# bal_part.net
KiCad netlist of a schematic drawn in EAGLE
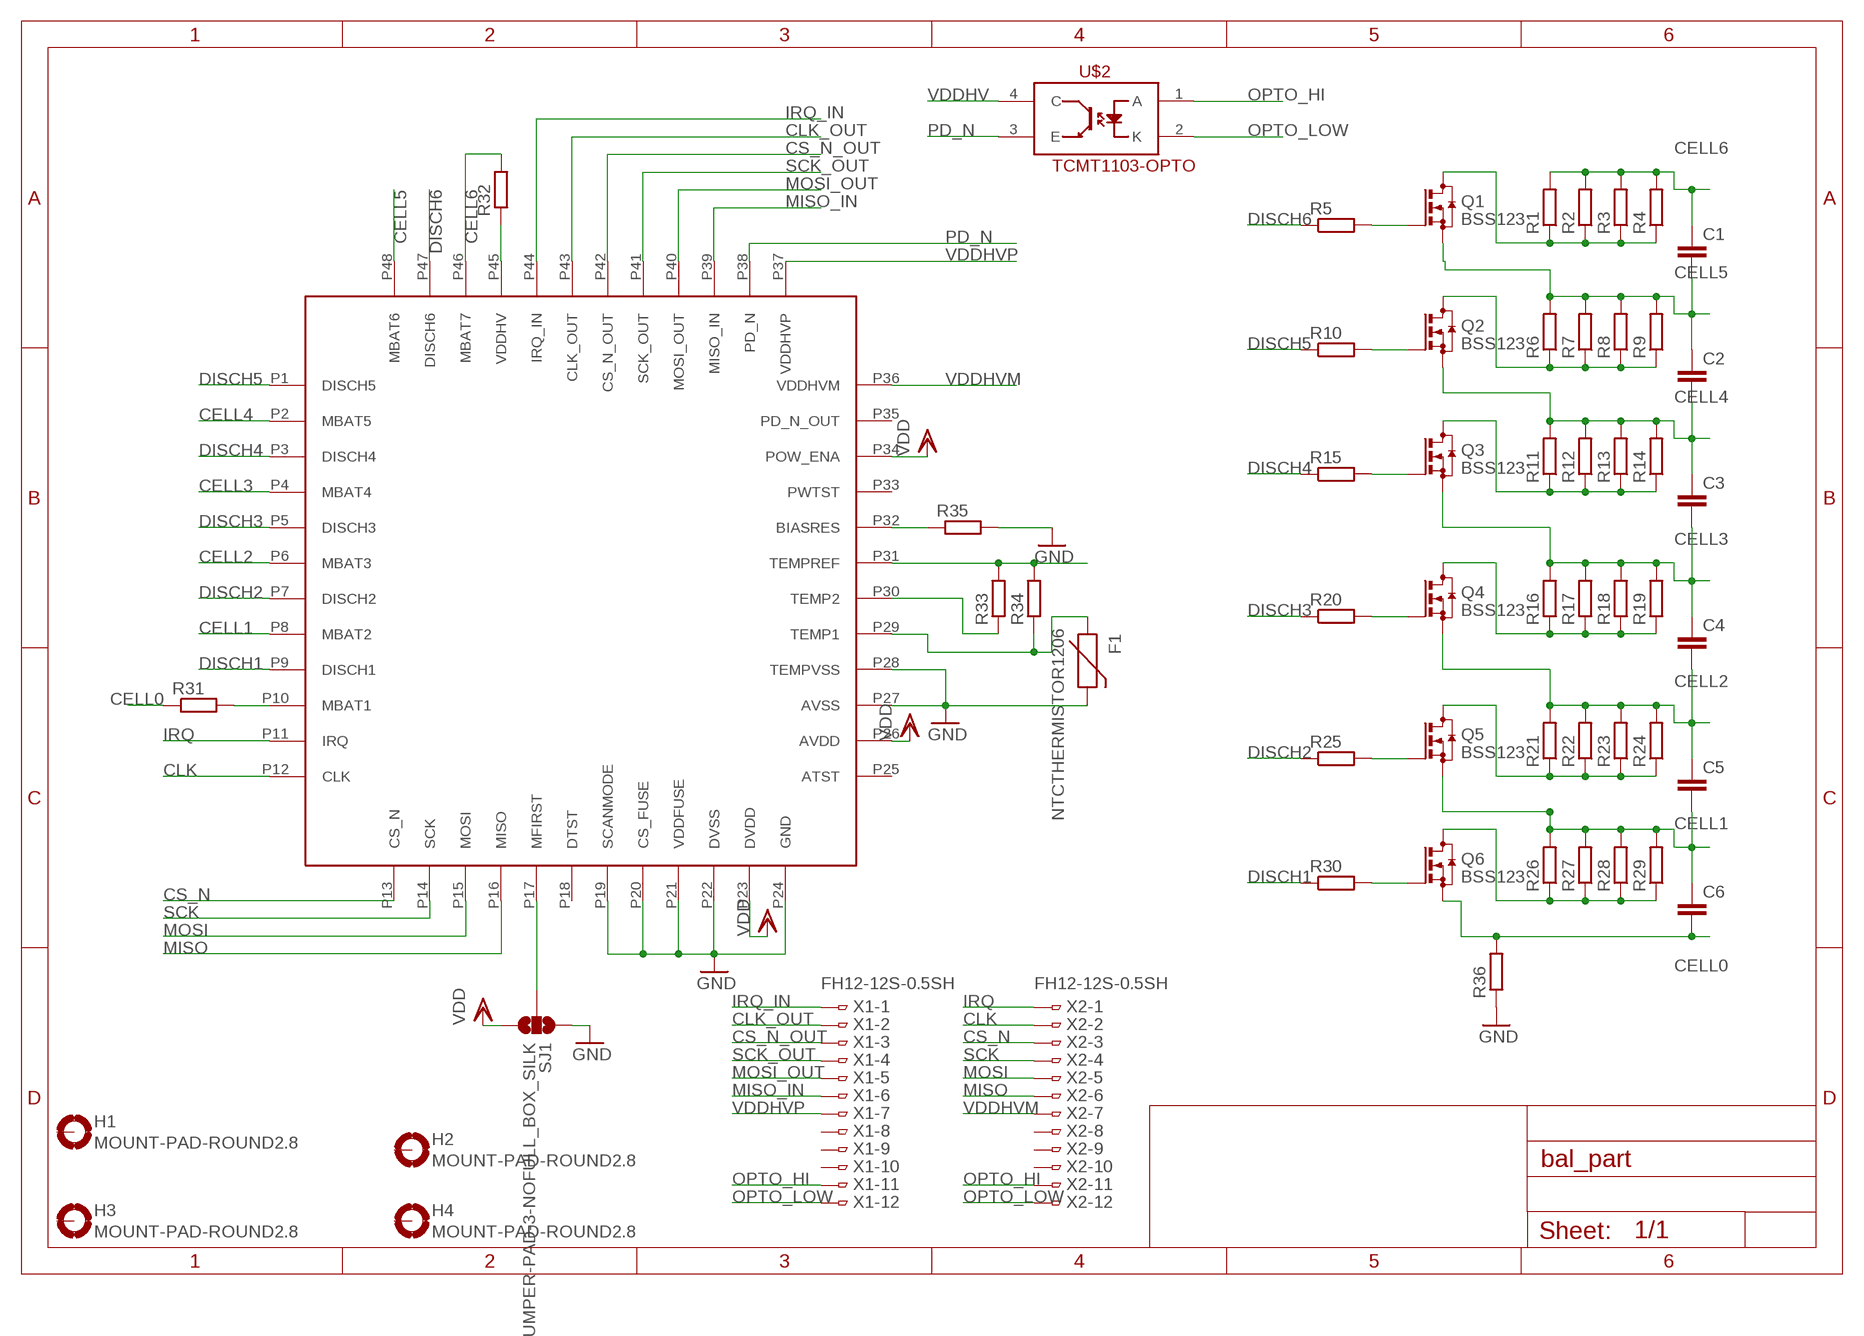
[diagram p0: schematic, sheet 1]

(export (version "E")
  (design (tool "Eeschema 10.0.6"))
  (components
    (comp (ref "C1")
      (value "C-EUC0805")
      (footprint "eagle-import:C0805")
      (libsource (lib "eagle-import") (part "C-EUC0805"))
    )
    (comp (ref "C2")
      (value "C-EUC0805")
      (footprint "eagle-import:C0805")
      (libsource (lib "eagle-import") (part "C-EUC0805"))
    )
    (comp (ref "C3")
      (value "C-EUC0805")
      (footprint "eagle-import:C0805")
      (libsource (lib "eagle-import") (part "C-EUC0805"))
    )
    (comp (ref "C4")
      (value "C-EUC0805")
      (footprint "eagle-import:C0805")
      (libsource (lib "eagle-import") (part "C-EUC0805"))
    )
    (comp (ref "C5")
      (value "C-EUC0805")
      (footprint "eagle-import:C0805")
      (libsource (lib "eagle-import") (part "C-EUC0805"))
    )
    (comp (ref "C6")
      (value "C-EUC0805")
      (footprint "eagle-import:C0805")
      (libsource (lib "eagle-import") (part "C-EUC0805"))
    )
    (comp (ref "F1")
      (value "NTCTHERMISTOR1206")
      (footprint "eagle-import:PTC-1206")
      (libsource (lib "eagle-import") (part "PTCTHERMISTOR1206"))
    )
    (comp (ref "H1")
      (value "MOUNT-PAD-ROUND2.8")
      (footprint "eagle-import:2,8-PAD")
      (libsource (lib "eagle-import") (part "MOUNT-PAD-ROUND2.8"))
    )
    (comp (ref "H2")
      (value "MOUNT-PAD-ROUND2.8")
      (footprint "eagle-import:2,8-PAD")
      (libsource (lib "eagle-import") (part "MOUNT-PAD-ROUND2.8"))
    )
    (comp (ref "H3")
      (value "MOUNT-PAD-ROUND2.8")
      (footprint "eagle-import:2,8-PAD")
      (libsource (lib "eagle-import") (part "MOUNT-PAD-ROUND2.8"))
    )
    (comp (ref "H4")
      (value "MOUNT-PAD-ROUND2.8")
      (footprint "eagle-import:2,8-PAD")
      (libsource (lib "eagle-import") (part "MOUNT-PAD-ROUND2.8"))
    )
    (comp (ref "Q1")
      (value "BSS123")
      (footprint "eagle-import:SOT23")
      (libsource (lib "eagle-import") (part "BSS123"))
    )
    (comp (ref "Q2")
      (value "BSS123")
      (footprint "eagle-import:SOT23")
      (libsource (lib "eagle-import") (part "BSS123"))
    )
    (comp (ref "Q3")
      (value "BSS123")
      (footprint "eagle-import:SOT23")
      (libsource (lib "eagle-import") (part "BSS123"))
    )
    (comp (ref "Q4")
      (value "BSS123")
      (footprint "eagle-import:SOT23")
      (libsource (lib "eagle-import") (part "BSS123"))
    )
    (comp (ref "Q5")
      (value "BSS123")
      (footprint "eagle-import:SOT23")
      (libsource (lib "eagle-import") (part "BSS123"))
    )
    (comp (ref "Q6")
      (value "BSS123")
      (footprint "eagle-import:SOT23")
      (libsource (lib "eagle-import") (part "BSS123"))
    )
    (comp (ref "R1")
      (value "R-EU_R1206")
      (footprint "eagle-import:R1206")
      (libsource (lib "eagle-import") (part "R-EU_R1206"))
    )
    (comp (ref "R2")
      (value "R-EU_R1206")
      (footprint "eagle-import:R1206")
      (libsource (lib "eagle-import") (part "R-EU_R1206"))
    )
    (comp (ref "R3")
      (value "R-EU_R1206")
      (footprint "eagle-import:R1206")
      (libsource (lib "eagle-import") (part "R-EU_R1206"))
    )
    (comp (ref "R4")
      (value "R-EU_R1206")
      (footprint "eagle-import:R1206")
      (libsource (lib "eagle-import") (part "R-EU_R1206"))
    )
    (comp (ref "R5")
      (value "R-EU_R0805")
      (footprint "eagle-import:R0805")
      (libsource (lib "eagle-import") (part "resistor_R-EU_R0805"))
    )
    (comp (ref "R6")
      (value "R-EU_R1206")
      (footprint "eagle-import:R1206")
      (libsource (lib "eagle-import") (part "R-EU_R1206"))
    )
    (comp (ref "R7")
      (value "R-EU_R1206")
      (footprint "eagle-import:R1206")
      (libsource (lib "eagle-import") (part "R-EU_R1206"))
    )
    (comp (ref "R8")
      (value "R-EU_R1206")
      (footprint "eagle-import:R1206")
      (libsource (lib "eagle-import") (part "R-EU_R1206"))
    )
    (comp (ref "R9")
      (value "R-EU_R1206")
      (footprint "eagle-import:R1206")
      (libsource (lib "eagle-import") (part "R-EU_R1206"))
    )
    (comp (ref "R10")
      (value "R-EU_R0805")
      (footprint "eagle-import:R0805")
      (libsource (lib "eagle-import") (part "resistor_R-EU_R0805"))
    )
    (comp (ref "R11")
      (value "R-EU_R1206")
      (footprint "eagle-import:R1206")
      (libsource (lib "eagle-import") (part "R-EU_R1206"))
    )
    (comp (ref "R12")
      (value "R-EU_R1206")
      (footprint "eagle-import:R1206")
      (libsource (lib "eagle-import") (part "R-EU_R1206"))
    )
    (comp (ref "R13")
      (value "R-EU_R1206")
      (footprint "eagle-import:R1206")
      (libsource (lib "eagle-import") (part "R-EU_R1206"))
    )
    (comp (ref "R14")
      (value "R-EU_R1206")
      (footprint "eagle-import:R1206")
      (libsource (lib "eagle-import") (part "R-EU_R1206"))
    )
    (comp (ref "R15")
      (value "R-EU_R0805")
      (footprint "eagle-import:R0805")
      (libsource (lib "eagle-import") (part "resistor_R-EU_R0805"))
    )
    (comp (ref "R16")
      (value "R-EU_R1206")
      (footprint "eagle-import:R1206")
      (libsource (lib "eagle-import") (part "R-EU_R1206"))
    )
    (comp (ref "R17")
      (value "R-EU_R1206")
      (footprint "eagle-import:R1206")
      (libsource (lib "eagle-import") (part "R-EU_R1206"))
    )
    (comp (ref "R18")
      (value "R-EU_R1206")
      (footprint "eagle-import:R1206")
      (libsource (lib "eagle-import") (part "R-EU_R1206"))
    )
    (comp (ref "R19")
      (value "R-EU_R1206")
      (footprint "eagle-import:R1206")
      (libsource (lib "eagle-import") (part "R-EU_R1206"))
    )
    (comp (ref "R20")
      (value "R-EU_R0805")
      (footprint "eagle-import:R0805")
      (libsource (lib "eagle-import") (part "resistor_R-EU_R0805"))
    )
    (comp (ref "R21")
      (value "R-EU_R1206")
      (footprint "eagle-import:R1206")
      (libsource (lib "eagle-import") (part "R-EU_R1206"))
    )
    (comp (ref "R22")
      (value "R-EU_R1206")
      (footprint "eagle-import:R1206")
      (libsource (lib "eagle-import") (part "R-EU_R1206"))
    )
    (comp (ref "R23")
      (value "R-EU_R1206")
      (footprint "eagle-import:R1206")
      (libsource (lib "eagle-import") (part "R-EU_R1206"))
    )
    (comp (ref "R24")
      (value "R-EU_R1206")
      (footprint "eagle-import:R1206")
      (libsource (lib "eagle-import") (part "R-EU_R1206"))
    )
    (comp (ref "R25")
      (value "R-EU_R0805")
      (footprint "eagle-import:R0805")
      (libsource (lib "eagle-import") (part "resistor_R-EU_R0805"))
    )
    (comp (ref "R26")
      (value "R-EU_R1206")
      (footprint "eagle-import:R1206")
      (libsource (lib "eagle-import") (part "R-EU_R1206"))
    )
    (comp (ref "R27")
      (value "R-EU_R1206")
      (footprint "eagle-import:R1206")
      (libsource (lib "eagle-import") (part "R-EU_R1206"))
    )
    (comp (ref "R28")
      (value "R-EU_R1206")
      (footprint "eagle-import:R1206")
      (libsource (lib "eagle-import") (part "R-EU_R1206"))
    )
    (comp (ref "R29")
      (value "R-EU_R1206")
      (footprint "eagle-import:R1206")
      (libsource (lib "eagle-import") (part "R-EU_R1206"))
    )
    (comp (ref "R30")
      (value "R-EU_R0805")
      (footprint "eagle-import:R0805")
      (libsource (lib "eagle-import") (part "resistor_R-EU_R0805"))
    )
    (comp (ref "R31")
      (value "R-EU_R0805")
      (footprint "eagle-import:R0805")
      (libsource (lib "eagle-import") (part "resistor_R-EU_R0805"))
    )
    (comp (ref "R32")
      (value "R-EU_R0805")
      (footprint "eagle-import:R0805")
      (libsource (lib "eagle-import") (part "resistor_R-EU_R0805"))
    )
    (comp (ref "R33")
      (value "R-EU_R0805")
      (footprint "eagle-import:R0805")
      (libsource (lib "eagle-import") (part "resistor_R-EU_R0805"))
    )
    (comp (ref "R34")
      (value "R-EU_R0805")
      (footprint "eagle-import:R0805")
      (libsource (lib "eagle-import") (part "resistor_R-EU_R0805"))
    )
    (comp (ref "R35")
      (value "R-EU_R0805")
      (footprint "eagle-import:R0805")
      (libsource (lib "eagle-import") (part "resistor_R-EU_R0805"))
    )
    (comp (ref "R36")
      (value "R-EU_R0805")
      (footprint "eagle-import:R0805")
      (libsource (lib "eagle-import") (part "resistor_R-EU_R0805"))
    )
    (comp (ref "SJ1")
      (value "JUMPER-PAD-3-NOFULL_BOX_SILK")
      (footprint "eagle-import:PAD-JUMPER-3-NO_YES_SILK_FULL_BOX")
      (libsource (lib "eagle-import") (part "JUMPER-PAD-3-NOFULL_BOX_SILK"))
    )
    (comp (ref "U$1")
      (value "ATA6870")
      (footprint "eagle-import:QFN48")
      (libsource (lib "eagle-import") (part "ATA6870"))
    )
    (comp (ref "U$2")
      (value "TCMT1103-OPTO")
      (footprint "eagle-import:SSOP-4")
      (libsource (lib "eagle-import") (part "TCMT1103-OPTO"))
    )
    (comp (ref "X1")
      (value "FH12-12S-0.5SH")
      (footprint "eagle-import:FH12-12S-0.5SH")
      (fields (field (name "MPN") "FH12-12S-0.5SH(55)"))
      (libsource (lib "eagle-import") (part "FH12-12S-0.5SH"))
    )
    (comp (ref "X2")
      (value "FH12-12S-0.5SH")
      (footprint "eagle-import:FH12-12S-0.5SH")
      (fields (field (name "MPN") "FH12-12S-0.5SH(55)"))
      (libsource (lib "eagle-import") (part "FH12-12S-0.5SH"))
    )
  )
  (nets
    (net (code "1") (name "/CELL0") (class "Default")
      (node (ref "C6") (pin "2") (pinfunction "2_2") (pintype "passive"))
      (node (ref "Q6") (pin "2") (pinfunction "S_2") (pintype "passive"))
      (node (ref "R31") (pin "1") (pinfunction "1_1") (pintype "passive"))
      (node (ref "R36") (pin "2") (pinfunction "2_2") (pintype "passive"))
    )
    (net (code "2") (name "/CELL1") (class "Default")
      (node (ref "C5") (pin "2") (pinfunction "2_2") (pintype "passive"))
      (node (ref "C6") (pin "1") (pinfunction "1_1") (pintype "passive"))
      (node (ref "Q5") (pin "2") (pinfunction "S_2") (pintype "passive"))
      (node (ref "R26") (pin "2") (pinfunction "2_2") (pintype "passive"))
      (node (ref "R27") (pin "2") (pinfunction "2_2") (pintype "passive"))
      (node (ref "R28") (pin "2") (pinfunction "2_2") (pintype "passive"))
      (node (ref "R29") (pin "2") (pinfunction "2_2") (pintype "passive"))
      (node (ref "U$1") (pin "P8") (pinfunction "MBAT2_P8") (pintype "bidirectional"))
    )
    (net (code "3") (name "/CELL2") (class "Default")
      (node (ref "C4") (pin "2") (pinfunction "2_2") (pintype "passive"))
      (node (ref "C5") (pin "1") (pinfunction "1_1") (pintype "passive"))
      (node (ref "Q4") (pin "2") (pinfunction "S_2") (pintype "passive"))
      (node (ref "R21") (pin "2") (pinfunction "2_2") (pintype "passive"))
      (node (ref "R22") (pin "2") (pinfunction "2_2") (pintype "passive"))
      (node (ref "R23") (pin "2") (pinfunction "2_2") (pintype "passive"))
      (node (ref "R24") (pin "2") (pinfunction "2_2") (pintype "passive"))
      (node (ref "U$1") (pin "P6") (pinfunction "MBAT3_P6") (pintype "bidirectional"))
    )
    (net (code "4") (name "/CELL3") (class "Default")
      (node (ref "C3") (pin "2") (pinfunction "2_2") (pintype "passive"))
      (node (ref "C4") (pin "1") (pinfunction "1_1") (pintype "passive"))
      (node (ref "Q3") (pin "2") (pinfunction "S_2") (pintype "passive"))
      (node (ref "R16") (pin "2") (pinfunction "2_2") (pintype "passive"))
      (node (ref "R17") (pin "2") (pinfunction "2_2") (pintype "passive"))
      (node (ref "R18") (pin "2") (pinfunction "2_2") (pintype "passive"))
      (node (ref "R19") (pin "2") (pinfunction "2_2") (pintype "passive"))
      (node (ref "U$1") (pin "P4") (pinfunction "MBAT4_P4") (pintype "bidirectional"))
    )
    (net (code "5") (name "/CELL4") (class "Default")
      (node (ref "C2") (pin "2") (pinfunction "2_2") (pintype "passive"))
      (node (ref "C3") (pin "1") (pinfunction "1_1") (pintype "passive"))
      (node (ref "Q2") (pin "2") (pinfunction "S_2") (pintype "passive"))
      (node (ref "R11") (pin "2") (pinfunction "2_2") (pintype "passive"))
      (node (ref "R12") (pin "2") (pinfunction "2_2") (pintype "passive"))
      (node (ref "R13") (pin "2") (pinfunction "2_2") (pintype "passive"))
      (node (ref "R14") (pin "2") (pinfunction "2_2") (pintype "passive"))
      (node (ref "U$1") (pin "P2") (pinfunction "MBAT5_P2") (pintype "bidirectional"))
    )
    (net (code "6") (name "/CELL5") (class "Default")
      (node (ref "C1") (pin "2") (pinfunction "2_2") (pintype "passive"))
      (node (ref "C2") (pin "1") (pinfunction "1_1") (pintype "passive"))
      (node (ref "Q1") (pin "2") (pinfunction "S_2") (pintype "passive"))
      (node (ref "R6") (pin "2") (pinfunction "2_2") (pintype "passive"))
      (node (ref "R7") (pin "2") (pinfunction "2_2") (pintype "passive"))
      (node (ref "R8") (pin "2") (pinfunction "2_2") (pintype "passive"))
      (node (ref "R9") (pin "2") (pinfunction "2_2") (pintype "passive"))
      (node (ref "U$1") (pin "P48") (pinfunction "MBAT6_P48") (pintype "bidirectional"))
    )
    (net (code "7") (name "/CELL6") (class "Default")
      (node (ref "C1") (pin "1") (pinfunction "1_1") (pintype "passive"))
      (node (ref "R1") (pin "2") (pinfunction "2_2") (pintype "passive"))
      (node (ref "R2") (pin "2") (pinfunction "2_2") (pintype "passive"))
      (node (ref "R3") (pin "2") (pinfunction "2_2") (pintype "passive"))
      (node (ref "R32") (pin "2") (pinfunction "2_2") (pintype "passive"))
      (node (ref "R4") (pin "2") (pinfunction "2_2") (pintype "passive"))
      (node (ref "U$1") (pin "P46") (pinfunction "MBAT7_P46") (pintype "bidirectional"))
    )
    (net (code "8") (name "/CLK") (class "Default")
      (node (ref "U$1") (pin "P12") (pinfunction "CLK_P12") (pintype "bidirectional"))
      (node (ref "X2") (pin "2") (pinfunction "1_2") (pintype "passive"))
    )
    (net (code "9") (name "/CLK_OUT") (class "Default")
      (node (ref "U$1") (pin "P43") (pinfunction "CLK_OUT_P43") (pintype "bidirectional"))
      (node (ref "X1") (pin "2") (pinfunction "1_2") (pintype "passive"))
    )
    (net (code "10") (name "/CS_N") (class "Default")
      (node (ref "U$1") (pin "P13") (pinfunction "CS_N_P13") (pintype "bidirectional"))
      (node (ref "X2") (pin "3") (pinfunction "1_3") (pintype "passive"))
    )
    (net (code "11") (name "/CS_N_OUT") (class "Default")
      (node (ref "U$1") (pin "P42") (pinfunction "CS_N_OUT_P42") (pintype "bidirectional"))
      (node (ref "X1") (pin "3") (pinfunction "1_3") (pintype "passive"))
    )
    (net (code "12") (name "/DISCH1") (class "Default")
      (node (ref "R30") (pin "1") (pinfunction "1_1") (pintype "passive"))
      (node (ref "U$1") (pin "P9") (pinfunction "DISCH1_P9") (pintype "bidirectional"))
    )
    (net (code "13") (name "/DISCH2") (class "Default")
      (node (ref "R25") (pin "1") (pinfunction "1_1") (pintype "passive"))
      (node (ref "U$1") (pin "P7") (pinfunction "DISCH2_P7") (pintype "bidirectional"))
    )
    (net (code "14") (name "/DISCH3") (class "Default")
      (node (ref "R20") (pin "1") (pinfunction "1_1") (pintype "passive"))
      (node (ref "U$1") (pin "P5") (pinfunction "DISCH3_P5") (pintype "bidirectional"))
    )
    (net (code "15") (name "/DISCH4") (class "Default")
      (node (ref "R15") (pin "1") (pinfunction "1_1") (pintype "passive"))
      (node (ref "U$1") (pin "P3") (pinfunction "DISCH4_P3") (pintype "bidirectional"))
    )
    (net (code "16") (name "/DISCH5") (class "Default")
      (node (ref "R10") (pin "1") (pinfunction "1_1") (pintype "passive"))
      (node (ref "U$1") (pin "P1") (pinfunction "DISCH5_P1") (pintype "bidirectional"))
    )
    (net (code "17") (name "/DISCH6") (class "Default")
      (node (ref "R5") (pin "1") (pinfunction "1_1") (pintype "passive"))
      (node (ref "U$1") (pin "P47") (pinfunction "DISCH6_P47") (pintype "bidirectional"))
    )
    (net (code "18") (name "/IRQ") (class "Default")
      (node (ref "U$1") (pin "P11") (pinfunction "IRQ_P11") (pintype "bidirectional"))
      (node (ref "X2") (pin "1") (pinfunction "1_1") (pintype "passive"))
    )
    (net (code "19") (name "/IRQ_IN") (class "Default")
      (node (ref "U$1") (pin "P44") (pinfunction "IRQ_IN_P44") (pintype "bidirectional"))
      (node (ref "X1") (pin "1") (pinfunction "1_1") (pintype "passive"))
    )
    (net (code "20") (name "/MISO") (class "Default")
      (node (ref "U$1") (pin "P16") (pinfunction "MISO_P16") (pintype "bidirectional"))
      (node (ref "X2") (pin "6") (pinfunction "1_6") (pintype "passive"))
    )
    (net (code "21") (name "/MISO_IN") (class "Default")
      (node (ref "U$1") (pin "P39") (pinfunction "MISO_IN_P39") (pintype "bidirectional"))
      (node (ref "X1") (pin "6") (pinfunction "1_6") (pintype "passive"))
    )
    (net (code "22") (name "/MOSI") (class "Default")
      (node (ref "U$1") (pin "P15") (pinfunction "MOSI_P15") (pintype "bidirectional"))
      (node (ref "X2") (pin "5") (pinfunction "1_5") (pintype "passive"))
    )
    (net (code "23") (name "/MOSI_OUT") (class "Default")
      (node (ref "U$1") (pin "P40") (pinfunction "MOSI_OUT_P40") (pintype "bidirectional"))
      (node (ref "X1") (pin "5") (pinfunction "1_5") (pintype "passive"))
    )
    (net (code "24") (name "/OPTO_HI") (class "Default")
      (node (ref "U$2") (pin "1") (pinfunction "A_1") (pintype "bidirectional"))
      (node (ref "X1") (pin "11") (pinfunction "1_11") (pintype "passive"))
      (node (ref "X2") (pin "11") (pinfunction "1_11") (pintype "passive"))
    )
    (net (code "25") (name "/OPTO_LOW") (class "Default")
      (node (ref "U$2") (pin "2") (pinfunction "K_2") (pintype "bidirectional"))
      (node (ref "X1") (pin "12") (pinfunction "1_12") (pintype "passive"))
      (node (ref "X2") (pin "12") (pinfunction "1_12") (pintype "passive"))
    )
    (net (code "26") (name "/PD_N") (class "Default")
      (node (ref "U$1") (pin "P38") (pinfunction "PD_N_P38") (pintype "bidirectional"))
      (node (ref "U$2") (pin "3") (pinfunction "E_3") (pintype "bidirectional"))
    )
    (net (code "27") (name "/SCK") (class "Default")
      (node (ref "U$1") (pin "P14") (pinfunction "SCK_P14") (pintype "bidirectional"))
      (node (ref "X2") (pin "4") (pinfunction "1_4") (pintype "passive"))
    )
    (net (code "28") (name "/SCK_OUT") (class "Default")
      (node (ref "U$1") (pin "P41") (pinfunction "SCK_OUT_P41") (pintype "bidirectional"))
      (node (ref "X1") (pin "4") (pinfunction "1_4") (pintype "passive"))
    )
    (net (code "29") (name "/VDDHV") (class "Default")
      (node (ref "R32") (pin "1") (pinfunction "1_1") (pintype "passive"))
      (node (ref "U$1") (pin "P45") (pinfunction "VDDHV_P45") (pintype "bidirectional"))
      (node (ref "U$2") (pin "4") (pinfunction "C_4") (pintype "bidirectional"))
    )
    (net (code "30") (name "/VDDHVM") (class "Default")
      (node (ref "U$1") (pin "P36") (pinfunction "VDDHVM_P36") (pintype "bidirectional"))
      (node (ref "X2") (pin "7") (pinfunction "1_7") (pintype "passive"))
    )
    (net (code "31") (name "/VDDHVP") (class "Default")
      (node (ref "U$1") (pin "P37") (pinfunction "VDDHVP_P37") (pintype "bidirectional"))
      (node (ref "X1") (pin "7") (pinfunction "1_7") (pintype "passive"))
    )
    (net (code "32") (name "GND") (class "Default")
      (node (ref "F1") (pin "2") (pinfunction "2_2") (pintype "bidirectional"))
      (node (ref "R35") (pin "2") (pinfunction "2_2") (pintype "passive"))
      (node (ref "R36") (pin "1") (pinfunction "1_1") (pintype "passive"))
      (node (ref "SJ1") (pin "1") (pinfunction "1_1") (pintype "passive"))
      (node (ref "U$1") (pin "P19") (pinfunction "SCANMODE_P19") (pintype "bidirectional"))
      (node (ref "U$1") (pin "P20") (pinfunction "CS_FUSE_P20") (pintype "bidirectional"))
      (node (ref "U$1") (pin "P21") (pinfunction "VDDFUSE_P21") (pintype "bidirectional"))
      (node (ref "U$1") (pin "P22") (pinfunction "DVSS_P22") (pintype "bidirectional"))
      (node (ref "U$1") (pin "P24") (pinfunction "GND_P24") (pintype "bidirectional"))
      (node (ref "U$1") (pin "P27") (pinfunction "AVSS_P27") (pintype "bidirectional"))
      (node (ref "U$1") (pin "P28") (pinfunction "TEMPVSS_P28") (pintype "bidirectional"))
    )
    (net (code "33") (name "Net-(Q1-D)") (class "Default")
      (node (ref "Q1") (pin "3") (pinfunction "D_3") (pintype "passive"))
      (node (ref "R1") (pin "1") (pinfunction "1_1") (pintype "passive"))
      (node (ref "R2") (pin "1") (pinfunction "1_1") (pintype "passive"))
      (node (ref "R3") (pin "1") (pinfunction "1_1") (pintype "passive"))
      (node (ref "R4") (pin "1") (pinfunction "1_1") (pintype "passive"))
    )
    (net (code "34") (name "Net-(Q1-G)") (class "Default")
      (node (ref "Q1") (pin "1") (pinfunction "G_1") (pintype "passive"))
      (node (ref "R5") (pin "2") (pinfunction "2_2") (pintype "passive"))
    )
    (net (code "35") (name "Net-(Q2-D)") (class "Default")
      (node (ref "Q2") (pin "3") (pinfunction "D_3") (pintype "passive"))
      (node (ref "R6") (pin "1") (pinfunction "1_1") (pintype "passive"))
      (node (ref "R7") (pin "1") (pinfunction "1_1") (pintype "passive"))
      (node (ref "R8") (pin "1") (pinfunction "1_1") (pintype "passive"))
      (node (ref "R9") (pin "1") (pinfunction "1_1") (pintype "passive"))
    )
    (net (code "36") (name "Net-(Q2-G)") (class "Default")
      (node (ref "Q2") (pin "1") (pinfunction "G_1") (pintype "passive"))
      (node (ref "R10") (pin "2") (pinfunction "2_2") (pintype "passive"))
    )
    (net (code "37") (name "Net-(Q3-D)") (class "Default")
      (node (ref "Q3") (pin "3") (pinfunction "D_3") (pintype "passive"))
      (node (ref "R11") (pin "1") (pinfunction "1_1") (pintype "passive"))
      (node (ref "R12") (pin "1") (pinfunction "1_1") (pintype "passive"))
      (node (ref "R13") (pin "1") (pinfunction "1_1") (pintype "passive"))
      (node (ref "R14") (pin "1") (pinfunction "1_1") (pintype "passive"))
    )
    (net (code "38") (name "Net-(Q3-G)") (class "Default")
      (node (ref "Q3") (pin "1") (pinfunction "G_1") (pintype "passive"))
      (node (ref "R15") (pin "2") (pinfunction "2_2") (pintype "passive"))
    )
    (net (code "39") (name "Net-(Q4-D)") (class "Default")
      (node (ref "Q4") (pin "3") (pinfunction "D_3") (pintype "passive"))
      (node (ref "R16") (pin "1") (pinfunction "1_1") (pintype "passive"))
      (node (ref "R17") (pin "1") (pinfunction "1_1") (pintype "passive"))
      (node (ref "R18") (pin "1") (pinfunction "1_1") (pintype "passive"))
      (node (ref "R19") (pin "1") (pinfunction "1_1") (pintype "passive"))
    )
    (net (code "40") (name "Net-(Q4-G)") (class "Default")
      (node (ref "Q4") (pin "1") (pinfunction "G_1") (pintype "passive"))
      (node (ref "R20") (pin "2") (pinfunction "2_2") (pintype "passive"))
    )
    (net (code "41") (name "Net-(Q5-D)") (class "Default")
      (node (ref "Q5") (pin "3") (pinfunction "D_3") (pintype "passive"))
      (node (ref "R21") (pin "1") (pinfunction "1_1") (pintype "passive"))
      (node (ref "R22") (pin "1") (pinfunction "1_1") (pintype "passive"))
      (node (ref "R23") (pin "1") (pinfunction "1_1") (pintype "passive"))
      (node (ref "R24") (pin "1") (pinfunction "1_1") (pintype "passive"))
    )
    (net (code "42") (name "Net-(Q5-G)") (class "Default")
      (node (ref "Q5") (pin "1") (pinfunction "G_1") (pintype "passive"))
      (node (ref "R25") (pin "2") (pinfunction "2_2") (pintype "passive"))
    )
    (net (code "43") (name "Net-(Q6-D)") (class "Default")
      (node (ref "Q6") (pin "3") (pinfunction "D_3") (pintype "passive"))
      (node (ref "R26") (pin "1") (pinfunction "1_1") (pintype "passive"))
      (node (ref "R27") (pin "1") (pinfunction "1_1") (pintype "passive"))
      (node (ref "R28") (pin "1") (pinfunction "1_1") (pintype "passive"))
      (node (ref "R29") (pin "1") (pinfunction "1_1") (pintype "passive"))
    )
    (net (code "44") (name "Net-(Q6-G)") (class "Default")
      (node (ref "Q6") (pin "1") (pinfunction "G_1") (pintype "passive"))
      (node (ref "R30") (pin "2") (pinfunction "2_2") (pintype "passive"))
    )
    (net (code "45") (name "Net-(U$1-BIASRES)") (class "Default")
      (node (ref "R35") (pin "1") (pinfunction "1_1") (pintype "passive"))
      (node (ref "U$1") (pin "P32") (pinfunction "BIASRES_P32") (pintype "bidirectional"))
    )
    (net (code "46") (name "Net-(U$1-MBAT1)") (class "Default")
      (node (ref "R31") (pin "2") (pinfunction "2_2") (pintype "passive"))
      (node (ref "U$1") (pin "P10") (pinfunction "MBAT1_P10") (pintype "bidirectional"))
    )
    (net (code "47") (name "Net-(U$1-MFIRST)") (class "Default")
      (node (ref "SJ1") (pin "2") (pinfunction "2_2") (pintype "passive"))
      (node (ref "U$1") (pin "P17") (pinfunction "MFIRST_P17") (pintype "bidirectional"))
    )
    (net (code "48") (name "Net-(U$1-TEMP1)") (class "Default")
      (node (ref "F1") (pin "1") (pinfunction "1_1") (pintype "bidirectional"))
      (node (ref "R34") (pin "1") (pinfunction "1_1") (pintype "passive"))
      (node (ref "U$1") (pin "P29") (pinfunction "TEMP1_P29") (pintype "bidirectional"))
    )
    (net (code "49") (name "Net-(U$1-TEMP2)") (class "Default")
      (node (ref "R33") (pin "1") (pinfunction "1_1") (pintype "passive"))
      (node (ref "U$1") (pin "P30") (pinfunction "TEMP2_P30") (pintype "bidirectional"))
    )
    (net (code "50") (name "Net-(U$1-TEMPREF)") (class "Default")
      (node (ref "R33") (pin "2") (pinfunction "2_2") (pintype "passive"))
      (node (ref "R34") (pin "2") (pinfunction "2_2") (pintype "passive"))
      (node (ref "U$1") (pin "P31") (pinfunction "TEMPREF_P31") (pintype "bidirectional"))
    )
    (net (code "51") (name "VDD") (class "Default")
      (node (ref "SJ1") (pin "3") (pinfunction "3_3") (pintype "passive"))
      (node (ref "U$1") (pin "P23") (pinfunction "DVDD_P23") (pintype "bidirectional"))
      (node (ref "U$1") (pin "P26") (pinfunction "AVDD_P26") (pintype "bidirectional"))
      (node (ref "U$1") (pin "P34") (pinfunction "POW_ENA_P34") (pintype "bidirectional"))
    )
    (net (code "52") (name "unconnected-(H1-MOUNT-PadB2,8)") (class "Default")
      (node (ref "H1") (pin "B2,8") (pinfunction "MOUNT_B2,8") (pintype "passive"))
    )
    (net (code "53") (name "unconnected-(H2-MOUNT-PadB2,8)") (class "Default")
      (node (ref "H2") (pin "B2,8") (pinfunction "MOUNT_B2,8") (pintype "passive"))
    )
    (net (code "54") (name "unconnected-(H3-MOUNT-PadB2,8)") (class "Default")
      (node (ref "H3") (pin "B2,8") (pinfunction "MOUNT_B2,8") (pintype "passive"))
    )
    (net (code "55") (name "unconnected-(H4-MOUNT-PadB2,8)") (class "Default")
      (node (ref "H4") (pin "B2,8") (pinfunction "MOUNT_B2,8") (pintype "passive"))
    )
    (net (code "56") (name "unconnected-(U$1-ATST-PadP25)") (class "Default")
      (node (ref "U$1") (pin "P25") (pinfunction "ATST_P25") (pintype "bidirectional"))
    )
    (net (code "57") (name "unconnected-(U$1-DTST-PadP18)") (class "Default")
      (node (ref "U$1") (pin "P18") (pinfunction "DTST_P18") (pintype "bidirectional"))
    )
    (net (code "58") (name "unconnected-(U$1-PD_N_OUT-PadP35)") (class "Default")
      (node (ref "U$1") (pin "P35") (pinfunction "PD_N_OUT_P35") (pintype "bidirectional"))
    )
    (net (code "59") (name "unconnected-(U$1-PWTST-PadP33)") (class "Default")
      (node (ref "U$1") (pin "P33") (pinfunction "PWTST_P33") (pintype "bidirectional"))
    )
    (net (code "60") (name "unconnected-(X1B-1-Pad10)") (class "Default")
      (node (ref "X1") (pin "10") (pinfunction "1_10") (pintype "passive"))
    )
    (net (code "61") (name "unconnected-(X1K-1-Pad8)") (class "Default")
      (node (ref "X1") (pin "8") (pinfunction "1_8") (pintype "passive"))
    )
    (net (code "62") (name "unconnected-(X1L-1-Pad9)") (class "Default")
      (node (ref "X1") (pin "9") (pinfunction "1_9") (pintype "passive"))
    )
    (net (code "63") (name "unconnected-(X2B-1-Pad10)") (class "Default")
      (node (ref "X2") (pin "10") (pinfunction "1_10") (pintype "passive"))
    )
    (net (code "64") (name "unconnected-(X2K-1-Pad8)") (class "Default")
      (node (ref "X2") (pin "8") (pinfunction "1_8") (pintype "passive"))
    )
    (net (code "65") (name "unconnected-(X2L-1-Pad9)") (class "Default")
      (node (ref "X2") (pin "9") (pinfunction "1_9") (pintype "passive"))
    )
  )
)
